# decimal-up-counter-d-flipflop.net
KiCad netlist of a schematic drawn in EasyEDA Pro
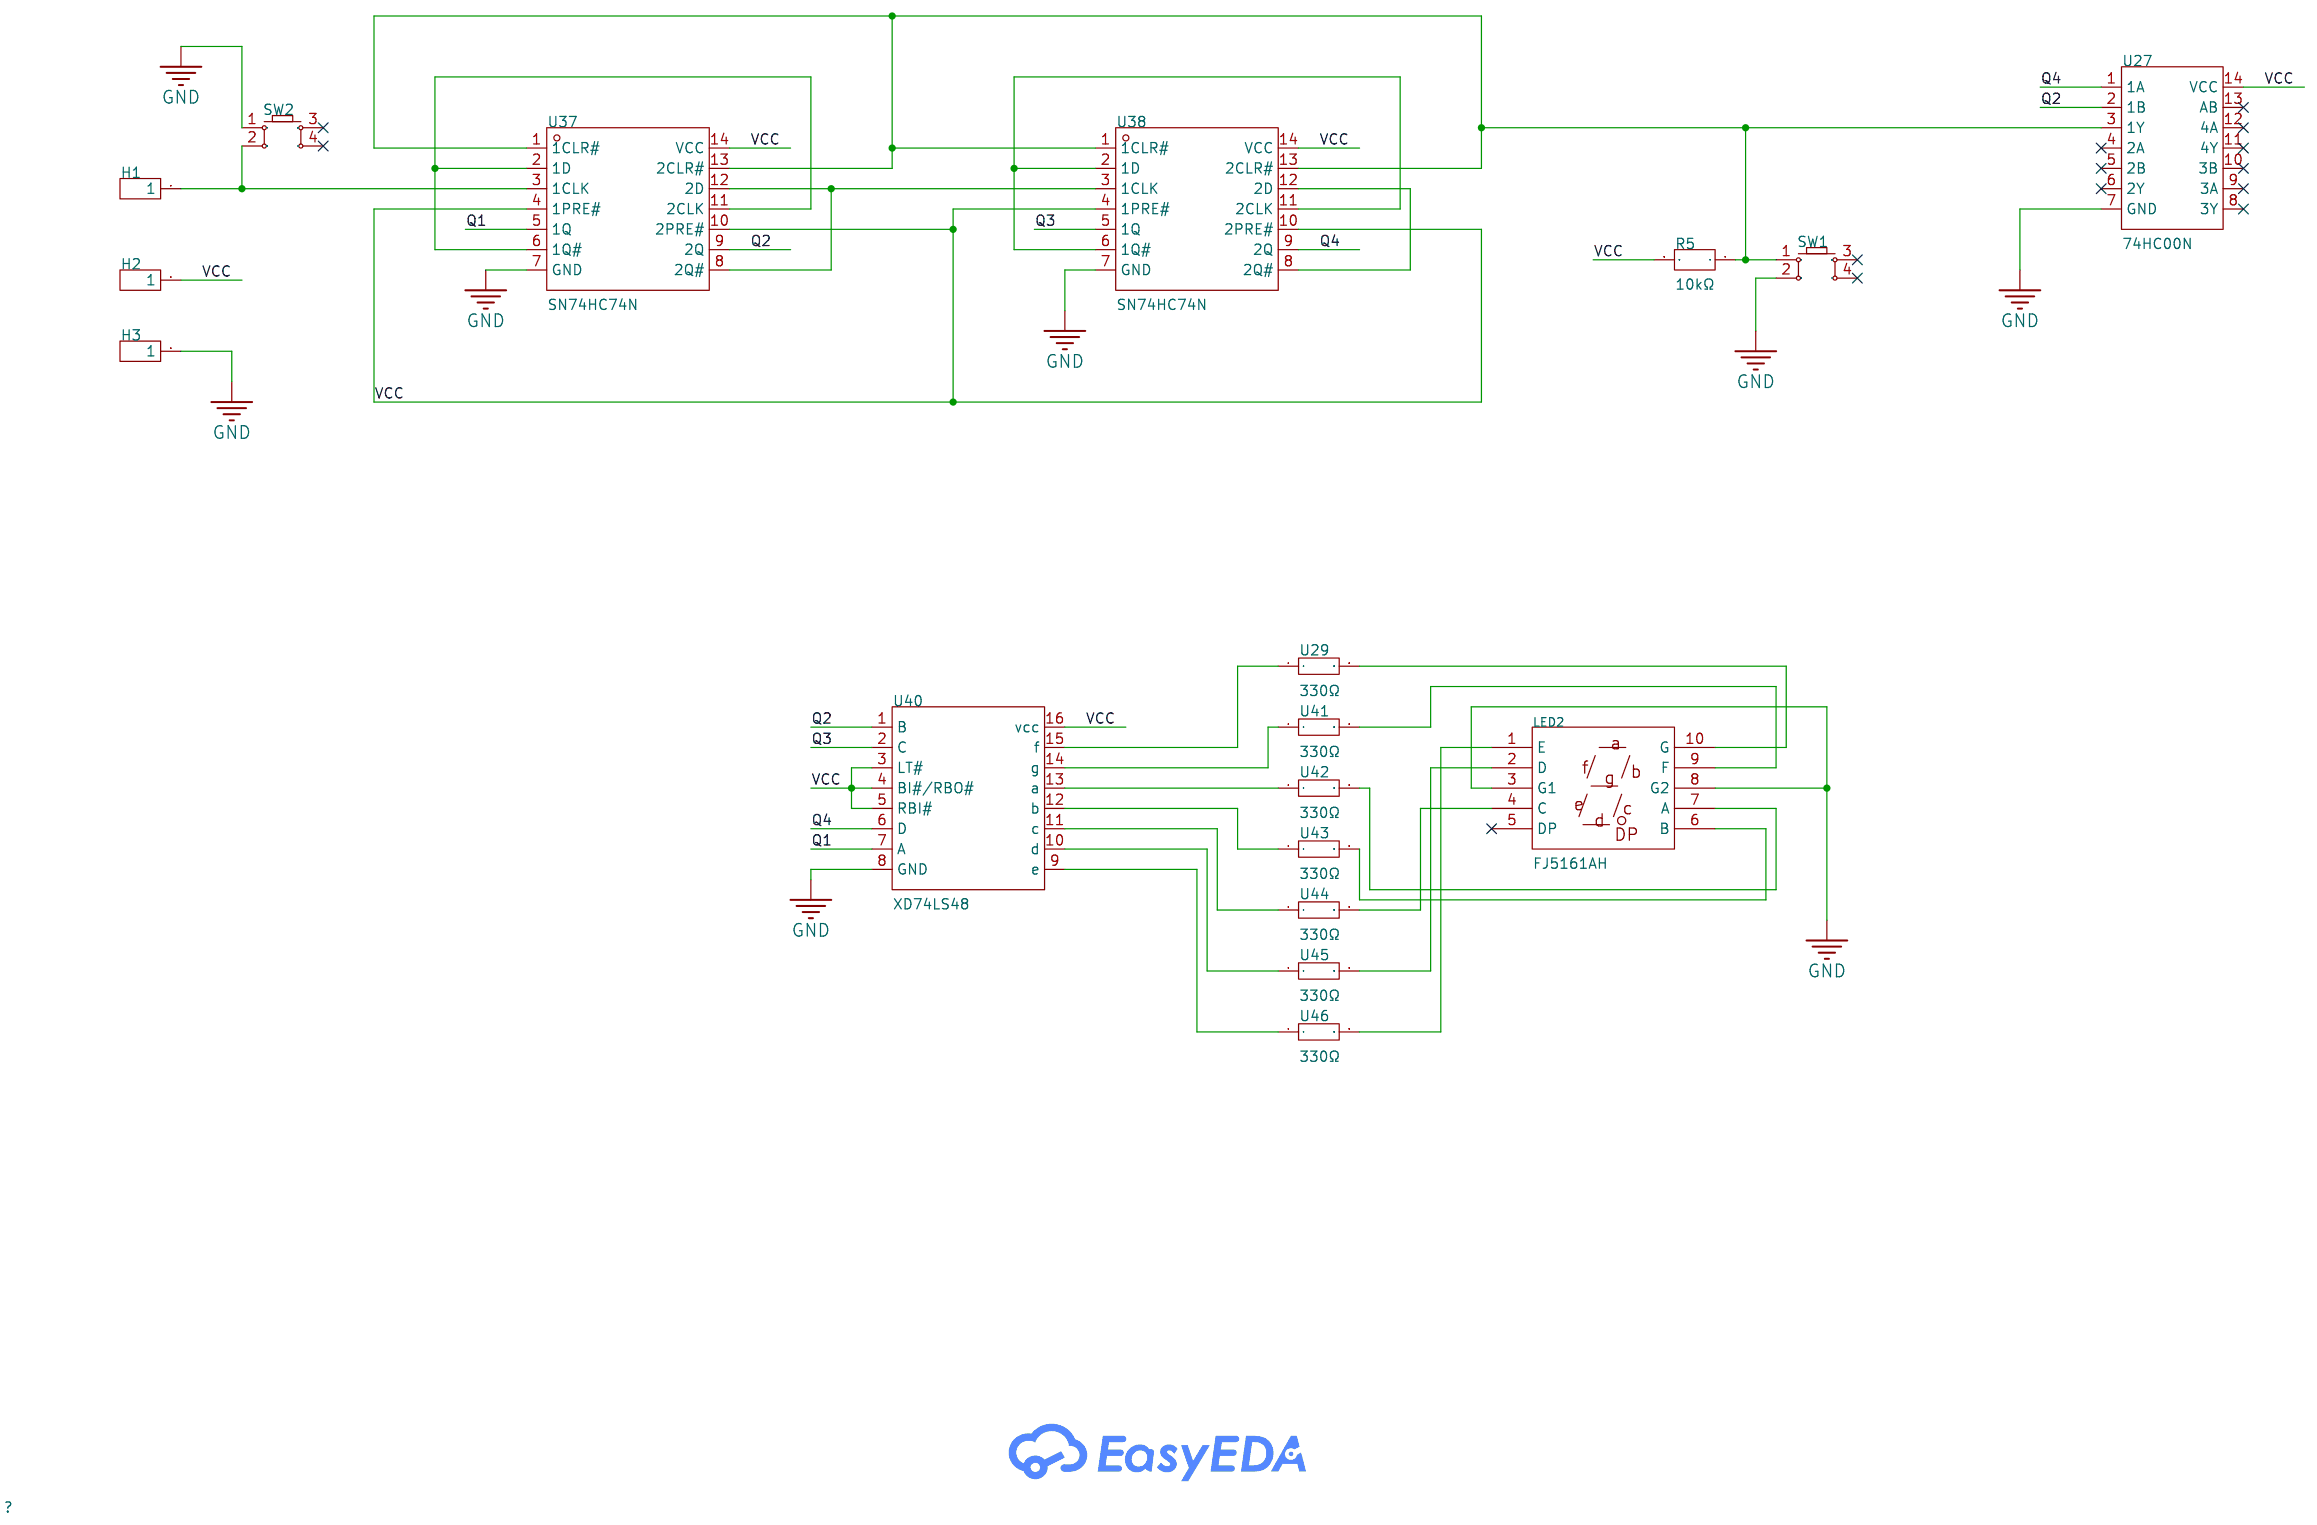
[diagram p0: schematic sheet]

(export (version "E")
  (design (tool "Eeschema 10.0.6"))
  (components
    (comp (ref "H1")
      (value "~")
      (footprint "easyedapro:HDR-TH_1P-V-M_XKB_X4611WV-01I-C28D40")
      (libsource (lib "easyedapro") (part "HDR_1x1"))
    )
    (comp (ref "H2")
      (value "~")
      (footprint "easyedapro:HDR-TH_1P-V-M_XKB_X4611WV-01I-C28D40")
      (libsource (lib "easyedapro") (part "HDR_1x1"))
    )
    (comp (ref "H3")
      (value "~")
      (footprint "easyedapro:HDR-TH_1P-V-M_XKB_X4611WV-01I-C28D40")
      (libsource (lib "easyedapro") (part "HDR_1x1"))
    )
    (comp (ref "LED2")
      (value "FJ5161AH")
      (footprint "easyedapro:LED-SEG-TH_10P-L12.6-W19.0-P2.54-S15.24-BL")
      (fields (field (name "Manufacturer") "志浩"))
      (libsource (lib "easyedapro") (part "FJ5161AH"))
    )
    (comp (ref "R5")
      (value "10kΩ")
      (footprint "easyedapro:RES-TH_BD2.5-L6.5-P10.50-D0.6")
      (fields
        (field (name "Manufacturer Part") "MBB02070C1002FCT00")
        (field (name "Manufacturer") "VISHAY(威世)")
      )
      (libsource (lib "easyedapro") (part "MBB02070C1002FCT00"))
    )
    (comp (ref "SW1")
      (value "~")
      (footprint "easyedapro:KEY-TH_4P-L6.0-W6.0-P3.90-LS6.5")
      (libsource (lib "easyedapro") (part "轻触按键"))
    )
    (comp (ref "SW2")
      (value "~")
      (footprint "easyedapro:KEY-TH_4P-L6.0-W6.0-P3.90-LS6.5")
      (libsource (lib "easyedapro") (part "轻触按键"))
    )
    (comp (ref "U27")
      (value "74HC00N")
      (footprint "easyedapro:DIP-14_L19.0-W7.0-P2.54-LS7.6-BL")
      (fields (field (name "Manufacturer") "HTC"))
      (libsource (lib "easyedapro") (part "74HC00N"))
    )
    (comp (ref "U29")
      (value "330Ω")
      (footprint "easyedapro:RES-TH_BD2.3-L7.1-P11.10-D0.6")
      (fields (field (name "Manufacturer Part") "RF25CT52A331J") (field (name "Manufacturer") "KOA"))
      (libsource (lib "easyedapro") (part "RF25CT52A331J"))
    )
    (comp (ref "U37")
      (value "SN74HC74N")
      (footprint "easyedapro:PDIP-14_L19.3-W6.4-P2.54-LS7.6-BL")
      (fields (field (name "Manufacturer") "TI(德州仪器)"))
      (libsource (lib "easyedapro") (part "SN74HC74N"))
    )
    (comp (ref "U38")
      (value "SN74HC74N")
      (footprint "easyedapro:PDIP-14_L19.3-W6.4-P2.54-LS7.6-BL")
      (fields (field (name "Manufacturer") "TI(德州仪器)"))
      (libsource (lib "easyedapro") (part "SN74HC74N"))
    )
    (comp (ref "U40")
      (value "XD74LS48")
      (footprint "easyedapro:DIP-16_L19.3-W6.4-P2.54-LS7.6-BL")
      (fields (field (name "Manufacturer") "XINLUDA(信路达)"))
      (libsource (lib "easyedapro") (part "XD74LS48"))
    )
    (comp (ref "U41")
      (value "330Ω")
      (footprint "easyedapro:RES-TH_BD2.3-L7.1-P11.10-D0.6")
      (fields (field (name "Manufacturer Part") "RF25CT52A331J") (field (name "Manufacturer") "KOA"))
      (libsource (lib "easyedapro") (part "RF25CT52A331J"))
    )
    (comp (ref "U42")
      (value "330Ω")
      (footprint "easyedapro:RES-TH_BD2.3-L7.1-P11.10-D0.6")
      (fields (field (name "Manufacturer Part") "RF25CT52A331J") (field (name "Manufacturer") "KOA"))
      (libsource (lib "easyedapro") (part "RF25CT52A331J"))
    )
    (comp (ref "U43")
      (value "330Ω")
      (footprint "easyedapro:RES-TH_BD2.3-L7.1-P11.10-D0.6")
      (fields (field (name "Manufacturer Part") "RF25CT52A331J") (field (name "Manufacturer") "KOA"))
      (libsource (lib "easyedapro") (part "RF25CT52A331J"))
    )
    (comp (ref "U44")
      (value "330Ω")
      (footprint "easyedapro:RES-TH_BD2.3-L7.1-P11.10-D0.6")
      (fields (field (name "Manufacturer Part") "RF25CT52A331J") (field (name "Manufacturer") "KOA"))
      (libsource (lib "easyedapro") (part "RF25CT52A331J"))
    )
    (comp (ref "U45")
      (value "330Ω")
      (footprint "easyedapro:RES-TH_BD2.3-L7.1-P11.10-D0.6")
      (fields (field (name "Manufacturer Part") "RF25CT52A331J") (field (name "Manufacturer") "KOA"))
      (libsource (lib "easyedapro") (part "RF25CT52A331J"))
    )
    (comp (ref "U46")
      (value "330Ω")
      (footprint "easyedapro:RES-TH_BD2.3-L7.1-P11.10-D0.6")
      (fields (field (name "Manufacturer Part") "RF25CT52A331J") (field (name "Manufacturer") "KOA"))
      (libsource (lib "easyedapro") (part "RF25CT52A331J"))
    )
  )
  (nets
    (net (code "1") (name "/Q1") (class "Default")
      (node (ref "U37") (pin "5") (pinfunction "1Q_5") (pintype "unspecified"))
      (node (ref "U40") (pin "7") (pinfunction "A_7") (pintype "unspecified"))
    )
    (net (code "2") (name "/Q2") (class "Default")
      (node (ref "U27") (pin "2") (pinfunction "1B_2") (pintype "unspecified"))
      (node (ref "U37") (pin "9") (pinfunction "2Q_9") (pintype "unspecified"))
      (node (ref "U40") (pin "1") (pinfunction "B_1") (pintype "unspecified"))
    )
    (net (code "3") (name "/Q3") (class "Default")
      (node (ref "U38") (pin "5") (pinfunction "1Q_5") (pintype "unspecified"))
      (node (ref "U40") (pin "2") (pinfunction "C_2") (pintype "unspecified"))
    )
    (net (code "4") (name "/Q4") (class "Default")
      (node (ref "U27") (pin "1") (pinfunction "1A_1") (pintype "unspecified"))
      (node (ref "U38") (pin "9") (pinfunction "2Q_9") (pintype "unspecified"))
      (node (ref "U40") (pin "6") (pinfunction "D_6") (pintype "unspecified"))
    )
    (net (code "5") (name "/VCC") (class "Default")
      (node (ref "H2") (pin "1") (pinfunction "1_1") (pintype "unspecified"))
      (node (ref "R5") (pin "2") (pinfunction "2_2") (pintype "unspecified"))
      (node (ref "U27") (pin "14") (pinfunction "VCC_14") (pintype "unspecified"))
      (node (ref "U37") (pin "10") (pinfunction "2PRE#_10") (pintype "unspecified"))
      (node (ref "U37") (pin "14") (pinfunction "VCC_14") (pintype "unspecified"))
      (node (ref "U37") (pin "4") (pinfunction "1PRE#_4") (pintype "unspecified"))
      (node (ref "U38") (pin "10") (pinfunction "2PRE#_10") (pintype "unspecified"))
      (node (ref "U38") (pin "14") (pinfunction "VCC_14") (pintype "unspecified"))
      (node (ref "U38") (pin "4") (pinfunction "1PRE#_4") (pintype "unspecified"))
      (node (ref "U40") (pin "16") (pinfunction "vcc_16") (pintype "unspecified"))
      (node (ref "U40") (pin "3") (pinfunction "LT#_3") (pintype "unspecified"))
      (node (ref "U40") (pin "4") (pinfunction "BI#/RBO#_4") (pintype "unspecified"))
      (node (ref "U40") (pin "5") (pinfunction "RBI#_5") (pintype "unspecified"))
    )
    (net (code "6") (name "GND") (class "Default")
      (node (ref "H3") (pin "1") (pinfunction "1_1") (pintype "unspecified"))
      (node (ref "LED2") (pin "3") (pinfunction "G1_3") (pintype "input"))
      (node (ref "LED2") (pin "8") (pinfunction "G2_8") (pintype "input"))
      (node (ref "SW1") (pin "2") (pinfunction "2_2") (pintype "input"))
      (node (ref "SW2") (pin "1") (pinfunction "1_1") (pintype "input"))
      (node (ref "U27") (pin "7") (pinfunction "GND_7") (pintype "unspecified"))
      (node (ref "U37") (pin "7") (pinfunction "GND_7") (pintype "unspecified"))
      (node (ref "U38") (pin "7") (pinfunction "GND_7") (pintype "unspecified"))
      (node (ref "U40") (pin "8") (pinfunction "GND_8") (pintype "unspecified"))
    )
    (net (code "7") (name "Net-(LED2-A)") (class "Default")
      (node (ref "LED2") (pin "7") (pinfunction "A_7") (pintype "input"))
      (node (ref "U42") (pin "2") (pinfunction "2_2") (pintype "unspecified"))
    )
    (net (code "8") (name "Net-(LED2-B)") (class "Default")
      (node (ref "LED2") (pin "6") (pinfunction "B_6") (pintype "input"))
      (node (ref "U43") (pin "2") (pinfunction "2_2") (pintype "unspecified"))
    )
    (net (code "9") (name "Net-(LED2-C)") (class "Default")
      (node (ref "LED2") (pin "4") (pinfunction "C_4") (pintype "input"))
      (node (ref "U44") (pin "2") (pinfunction "2_2") (pintype "unspecified"))
    )
    (net (code "10") (name "Net-(LED2-D)") (class "Default")
      (node (ref "LED2") (pin "2") (pinfunction "D_2") (pintype "input"))
      (node (ref "U45") (pin "2") (pinfunction "2_2") (pintype "unspecified"))
    )
    (net (code "11") (name "Net-(LED2-E)") (class "Default")
      (node (ref "LED2") (pin "1") (pinfunction "E_1") (pintype "input"))
      (node (ref "U46") (pin "2") (pinfunction "2_2") (pintype "unspecified"))
    )
    (net (code "12") (name "Net-(LED2-F)") (class "Default")
      (node (ref "LED2") (pin "9") (pinfunction "F_9") (pintype "input"))
      (node (ref "U41") (pin "2") (pinfunction "2_2") (pintype "unspecified"))
    )
    (net (code "13") (name "Net-(LED2-G)") (class "Default")
      (node (ref "LED2") (pin "10") (pinfunction "G_10") (pintype "input"))
      (node (ref "U29") (pin "2") (pinfunction "2_2") (pintype "unspecified"))
    )
    (net (code "14") (name "Net-(U27-1Y)") (class "Default")
      (node (ref "R5") (pin "1") (pinfunction "1_1") (pintype "unspecified"))
      (node (ref "SW1") (pin "1") (pinfunction "1_1") (pintype "input"))
      (node (ref "U27") (pin "3") (pinfunction "1Y_3") (pintype "unspecified"))
      (node (ref "U37") (pin "1") (pinfunction "1CLR#_1") (pintype "unspecified"))
      (node (ref "U37") (pin "13") (pinfunction "2CLR#_13") (pintype "unspecified"))
      (node (ref "U38") (pin "1") (pinfunction "1CLR#_1") (pintype "unspecified"))
      (node (ref "U38") (pin "13") (pinfunction "2CLR#_13") (pintype "unspecified"))
    )
    (net (code "15") (name "Net-(U37-1CLK)") (class "Default")
      (node (ref "H1") (pin "1") (pinfunction "1_1") (pintype "unspecified"))
      (node (ref "SW2") (pin "2") (pinfunction "2_2") (pintype "input"))
      (node (ref "U37") (pin "3") (pinfunction "1CLK_3") (pintype "unspecified"))
    )
    (net (code "16") (name "Net-(U37-1D)") (class "Default")
      (node (ref "U37") (pin "11") (pinfunction "2CLK_11") (pintype "unspecified"))
      (node (ref "U37") (pin "2") (pinfunction "1D_2") (pintype "unspecified"))
      (node (ref "U37") (pin "6") (pinfunction "1Q#_6") (pintype "unspecified"))
    )
    (net (code "17") (name "Net-(U37-2D)") (class "Default")
      (node (ref "U37") (pin "12") (pinfunction "2D_12") (pintype "unspecified"))
      (node (ref "U37") (pin "8") (pinfunction "2Q#_8") (pintype "unspecified"))
      (node (ref "U38") (pin "3") (pinfunction "1CLK_3") (pintype "unspecified"))
    )
    (net (code "18") (name "Net-(U38-1D)") (class "Default")
      (node (ref "U38") (pin "11") (pinfunction "2CLK_11") (pintype "unspecified"))
      (node (ref "U38") (pin "2") (pinfunction "1D_2") (pintype "unspecified"))
      (node (ref "U38") (pin "6") (pinfunction "1Q#_6") (pintype "unspecified"))
    )
    (net (code "19") (name "Net-(U38-2D)") (class "Default")
      (node (ref "U38") (pin "12") (pinfunction "2D_12") (pintype "unspecified"))
      (node (ref "U38") (pin "8") (pinfunction "2Q#_8") (pintype "unspecified"))
    )
    (net (code "20") (name "Net-(U40-a)") (class "Default")
      (node (ref "U40") (pin "13") (pinfunction "a_13") (pintype "unspecified"))
      (node (ref "U42") (pin "1") (pinfunction "1_1") (pintype "unspecified"))
    )
    (net (code "21") (name "Net-(U40-b)") (class "Default")
      (node (ref "U40") (pin "12") (pinfunction "b_12") (pintype "unspecified"))
      (node (ref "U43") (pin "1") (pinfunction "1_1") (pintype "unspecified"))
    )
    (net (code "22") (name "Net-(U40-c)") (class "Default")
      (node (ref "U40") (pin "11") (pinfunction "c_11") (pintype "unspecified"))
      (node (ref "U44") (pin "1") (pinfunction "1_1") (pintype "unspecified"))
    )
    (net (code "23") (name "Net-(U40-d)") (class "Default")
      (node (ref "U40") (pin "10") (pinfunction "d_10") (pintype "unspecified"))
      (node (ref "U45") (pin "1") (pinfunction "1_1") (pintype "unspecified"))
    )
    (net (code "24") (name "Net-(U40-e)") (class "Default")
      (node (ref "U40") (pin "9") (pinfunction "e_9") (pintype "unspecified"))
      (node (ref "U46") (pin "1") (pinfunction "1_1") (pintype "unspecified"))
    )
    (net (code "25") (name "Net-(U40-f)") (class "Default")
      (node (ref "U29") (pin "1") (pinfunction "1_1") (pintype "unspecified"))
      (node (ref "U40") (pin "15") (pinfunction "f_15") (pintype "unspecified"))
    )
    (net (code "26") (name "Net-(U40-g)") (class "Default")
      (node (ref "U40") (pin "14") (pinfunction "g_14") (pintype "unspecified"))
      (node (ref "U41") (pin "1") (pinfunction "1_1") (pintype "unspecified"))
    )
    (net (code "27") (name "unconnected-(LED2-DP-Pad5)") (class "Default")
      (node (ref "LED2") (pin "5") (pinfunction "DP_5") (pintype "input+no_connect"))
    )
    (net (code "28") (name "unconnected-(SW1-Pad3)") (class "Default")
      (node (ref "SW1") (pin "3") (pinfunction "3_3") (pintype "input+no_connect"))
    )
    (net (code "29") (name "unconnected-(SW1-Pad4)") (class "Default")
      (node (ref "SW1") (pin "4") (pinfunction "4_4") (pintype "input+no_connect"))
    )
    (net (code "30") (name "unconnected-(SW2-Pad3)") (class "Default")
      (node (ref "SW2") (pin "3") (pinfunction "3_3") (pintype "input+no_connect"))
    )
    (net (code "31") (name "unconnected-(SW2-Pad4)") (class "Default")
      (node (ref "SW2") (pin "4") (pinfunction "4_4") (pintype "input+no_connect"))
    )
    (net (code "32") (name "unconnected-(U27-2A-Pad4)") (class "Default")
      (node (ref "U27") (pin "4") (pinfunction "2A_4") (pintype "unspecified+no_connect"))
    )
    (net (code "33") (name "unconnected-(U27-2B-Pad5)") (class "Default")
      (node (ref "U27") (pin "5") (pinfunction "2B_5") (pintype "unspecified+no_connect"))
    )
    (net (code "34") (name "unconnected-(U27-2Y-Pad6)") (class "Default")
      (node (ref "U27") (pin "6") (pinfunction "2Y_6") (pintype "unspecified+no_connect"))
    )
    (net (code "35") (name "unconnected-(U27-3A-Pad9)") (class "Default")
      (node (ref "U27") (pin "9") (pinfunction "3A_9") (pintype "unspecified+no_connect"))
    )
    (net (code "36") (name "unconnected-(U27-3B-Pad10)") (class "Default")
      (node (ref "U27") (pin "10") (pinfunction "3B_10") (pintype "unspecified+no_connect"))
    )
    (net (code "37") (name "unconnected-(U27-3Y-Pad8)") (class "Default")
      (node (ref "U27") (pin "8") (pinfunction "3Y_8") (pintype "unspecified+no_connect"))
    )
    (net (code "38") (name "unconnected-(U27-4A-Pad12)") (class "Default")
      (node (ref "U27") (pin "12") (pinfunction "4A_12") (pintype "unspecified+no_connect"))
    )
    (net (code "39") (name "unconnected-(U27-4Y-Pad11)") (class "Default")
      (node (ref "U27") (pin "11") (pinfunction "4Y_11") (pintype "unspecified+no_connect"))
    )
    (net (code "40") (name "unconnected-(U27-AB-Pad13)") (class "Default")
      (node (ref "U27") (pin "13") (pinfunction "AB_13") (pintype "unspecified+no_connect"))
    )
  )
)
